# ai_breakout_ads1115.net
KiCad netlist of a schematic drawn in EAGLE
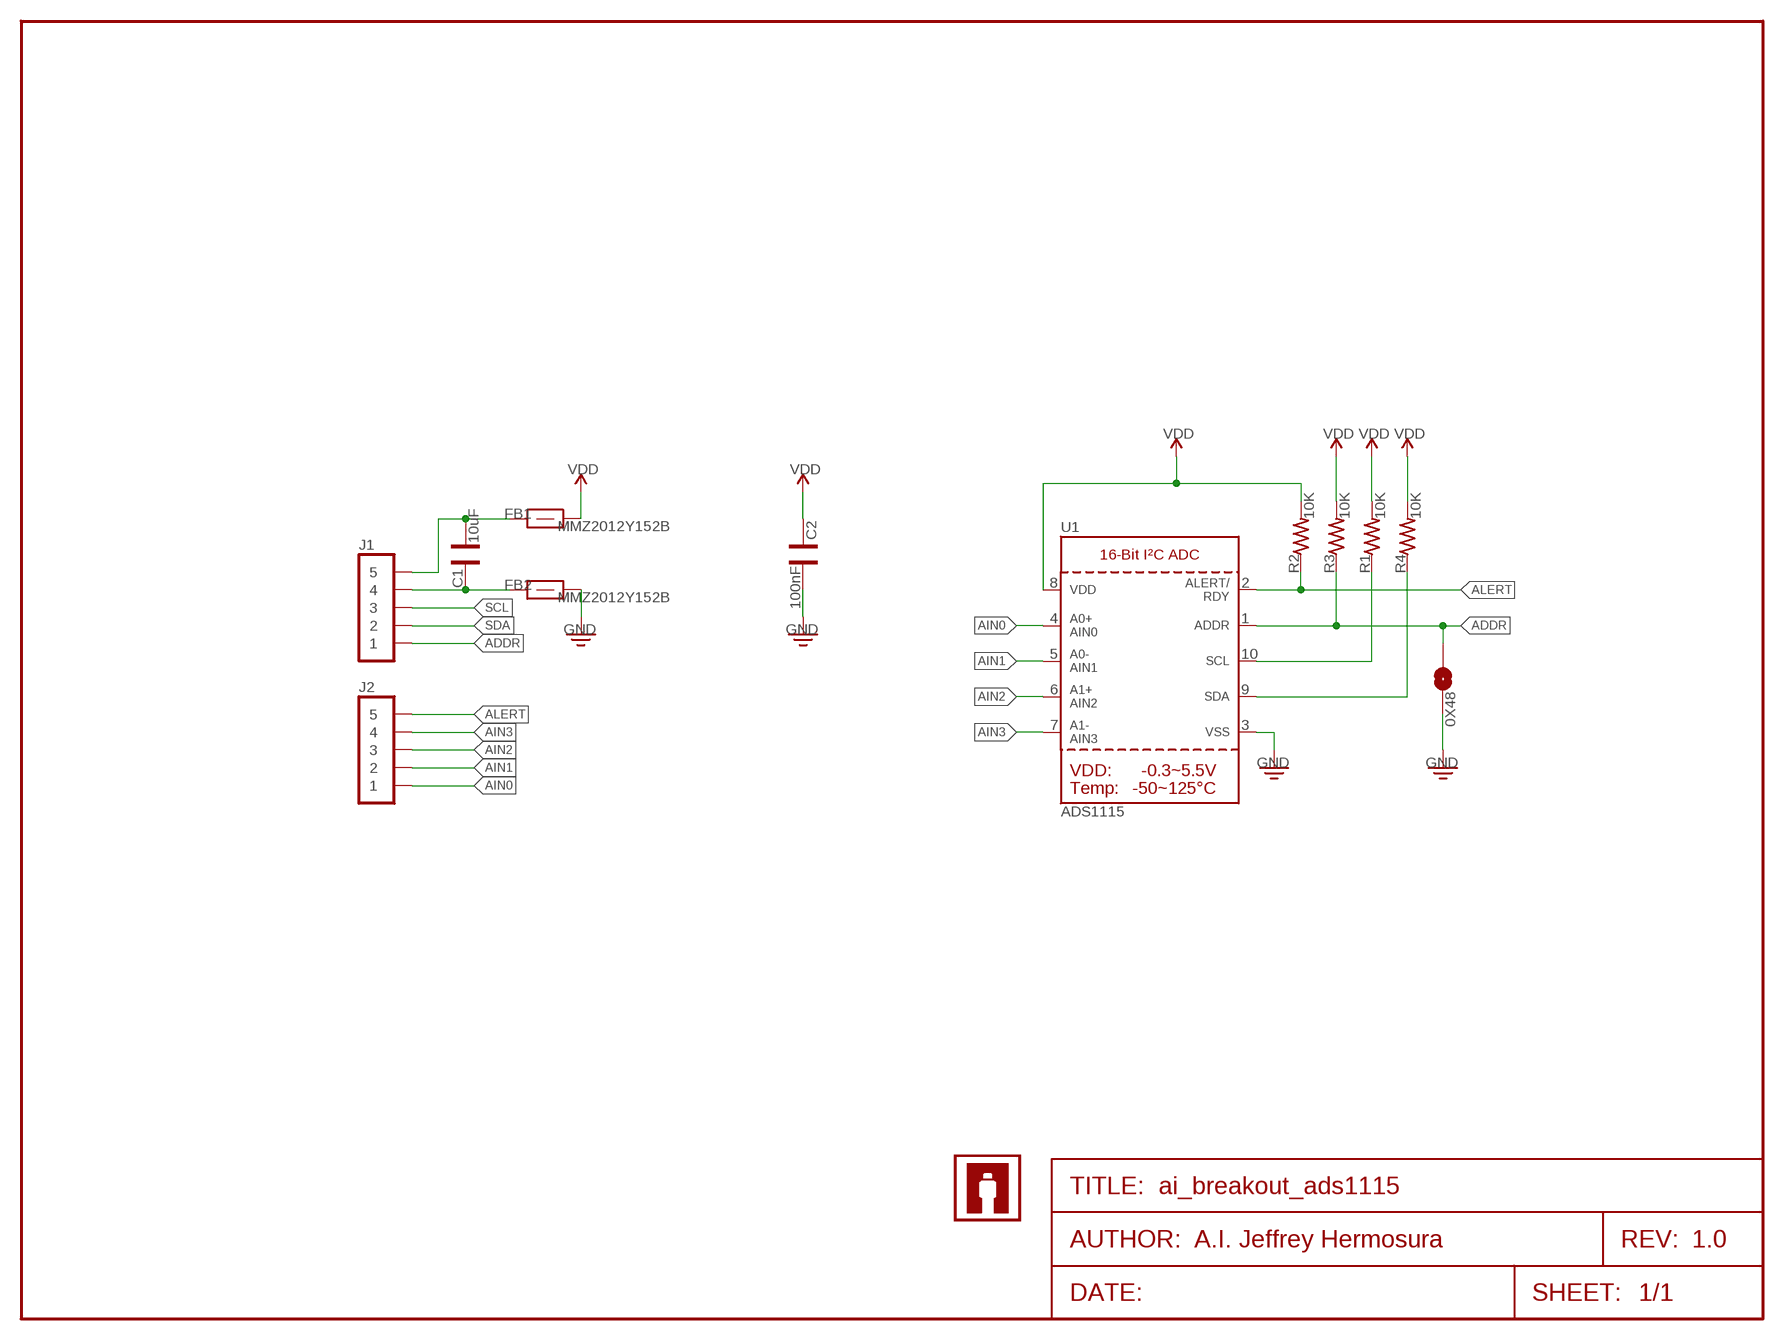
[diagram p0: schematic, sheet 1]

(export (version "E")
  (design (tool "Eeschema 10.0.6"))
  (components
    (comp (ref "0X48")
      (value "1X02-SJ-NO")
      (footprint "eagle-import:1X02-SJ-NO")
      (libsource (lib "eagle-import") (part "1X02-SJ-NO"))
    )
    (comp (ref "C1")
      (value "10uF")
      (footprint "eagle-import:CAP-0603")
      (libsource (lib "eagle-import") (part "CAP0603"))
    )
    (comp (ref "C2")
      (value "100nF")
      (footprint "eagle-import:CAP-0603")
      (libsource (lib "eagle-import") (part "CAP0603"))
    )
    (comp (ref "FB1")
      (value "MMZ2012Y152B")
      (footprint "eagle-import:FB-0603")
      (libsource (lib "eagle-import") (part "FB"))
    )
    (comp (ref "FB2")
      (value "MMZ2012Y152B")
      (footprint "eagle-import:FB-0603")
      (libsource (lib "eagle-import") (part "FB"))
    )
    (comp (ref "J1")
      (value "1X05")
      (footprint "eagle-import:1X05")
      (libsource (lib "eagle-import") (part "1X05"))
    )
    (comp (ref "J2")
      (value "1X05NOFIRST")
      (footprint "eagle-import:1X05-NOFIRST")
      (libsource (lib "eagle-import") (part "1X05NOFIRST"))
    )
    (comp (ref "R1")
      (value "10K")
      (footprint "eagle-import:RES-0603")
      (libsource (lib "eagle-import") (part "RES0603"))
    )
    (comp (ref "R2")
      (value "10K")
      (footprint "eagle-import:RES-0603")
      (libsource (lib "eagle-import") (part "RES0603"))
    )
    (comp (ref "R3")
      (value "10K")
      (footprint "eagle-import:RES-0603")
      (libsource (lib "eagle-import") (part "RES0603"))
    )
    (comp (ref "R4")
      (value "10K")
      (footprint "eagle-import:RES-0603")
      (libsource (lib "eagle-import") (part "RES0603"))
    )
    (comp (ref "U$2")
      (value "AI-LOGOXS")
      (footprint "eagle-import:AI-LOGO-XS")
      (libsource (lib "eagle-import") (part "AI-LOGOXS"))
    )
    (comp (ref "U1")
      (value "ADS1115")
      (footprint "eagle-import:MSOP10")
      (libsource (lib "eagle-import") (part "ADS1115"))
    )
  )
  (nets
    (net (code "1") (name "ADDR") (class "Default")
      (node (ref "0X48") (pin "1") (pinfunction "1_1") (pintype "passive"))
      (node (ref "J1") (pin "1") (pinfunction "1_1") (pintype "bidirectional"))
      (node (ref "R3") (pin "1") (pinfunction "1_1") (pintype "passive"))
      (node (ref "U1") (pin "1") (pinfunction "ADDR_1") (pintype "bidirectional"))
    )
    (net (code "2") (name "AIN0") (class "Default")
      (node (ref "J2") (pin "1") (pinfunction "1_1") (pintype "bidirectional"))
      (node (ref "U1") (pin "4") (pinfunction "AIN0_4") (pintype "bidirectional"))
    )
    (net (code "3") (name "AIN1") (class "Default")
      (node (ref "J2") (pin "2") (pinfunction "2_2") (pintype "bidirectional"))
      (node (ref "U1") (pin "5") (pinfunction "AIN1_5") (pintype "bidirectional"))
    )
    (net (code "4") (name "AIN2") (class "Default")
      (node (ref "J2") (pin "3") (pinfunction "3_3") (pintype "bidirectional"))
      (node (ref "U1") (pin "6") (pinfunction "AIN2_6") (pintype "bidirectional"))
    )
    (net (code "5") (name "AIN3") (class "Default")
      (node (ref "J2") (pin "4") (pinfunction "4_4") (pintype "bidirectional"))
      (node (ref "U1") (pin "7") (pinfunction "AIN3_7") (pintype "bidirectional"))
    )
    (net (code "6") (name "ALERT") (class "Default")
      (node (ref "J2") (pin "5") (pinfunction "5_5") (pintype "bidirectional"))
      (node (ref "R2") (pin "1") (pinfunction "1_1") (pintype "passive"))
      (node (ref "U1") (pin "2") (pinfunction "ALERT/RDY_2") (pintype "bidirectional"))
    )
    (net (code "7") (name "GND") (class "Default")
      (node (ref "0X48") (pin "2") (pinfunction "2_2") (pintype "passive"))
      (node (ref "C2") (pin "1") (pinfunction "1_1") (pintype "passive"))
      (node (ref "FB2") (pin "2") (pinfunction "P$2_2") (pintype "bidirectional"))
      (node (ref "U1") (pin "3") (pinfunction "VSS_3") (pintype "bidirectional"))
    )
    (net (code "8") (name "Net-(FB1-P$1)") (class "Default")
      (node (ref "C1") (pin "1") (pinfunction "1_1") (pintype "passive"))
      (node (ref "FB1") (pin "1") (pinfunction "P$1_1") (pintype "passive"))
      (node (ref "J1") (pin "5") (pinfunction "5_5") (pintype "bidirectional"))
    )
    (net (code "9") (name "Net-(FB2-P$1)") (class "Default")
      (node (ref "C1") (pin "2") (pinfunction "2_2") (pintype "passive"))
      (node (ref "FB2") (pin "1") (pinfunction "P$1_1") (pintype "passive"))
      (node (ref "J1") (pin "4") (pinfunction "4_4") (pintype "bidirectional"))
    )
    (net (code "10") (name "SCL") (class "Default")
      (node (ref "J1") (pin "3") (pinfunction "3_3") (pintype "bidirectional"))
      (node (ref "R1") (pin "1") (pinfunction "1_1") (pintype "passive"))
      (node (ref "U1") (pin "10") (pinfunction "SCL_10") (pintype "bidirectional"))
    )
    (net (code "11") (name "SDA") (class "Default")
      (node (ref "J1") (pin "2") (pinfunction "2_2") (pintype "bidirectional"))
      (node (ref "R4") (pin "1") (pinfunction "1_1") (pintype "passive"))
      (node (ref "U1") (pin "9") (pinfunction "SDA_9") (pintype "bidirectional"))
    )
    (net (code "12") (name "VDD") (class "Default")
      (node (ref "C2") (pin "2") (pinfunction "2_2") (pintype "passive"))
      (node (ref "FB1") (pin "2") (pinfunction "P$2_2") (pintype "bidirectional"))
      (node (ref "R1") (pin "2") (pinfunction "2_2") (pintype "passive"))
      (node (ref "R2") (pin "2") (pinfunction "2_2") (pintype "passive"))
      (node (ref "R3") (pin "2") (pinfunction "2_2") (pintype "passive"))
      (node (ref "R4") (pin "2") (pinfunction "2_2") (pintype "passive"))
      (node (ref "U1") (pin "8") (pinfunction "VDD_8") (pintype "bidirectional"))
    )
  )
)
